# IO_master_nano.net
KiCad netlist of a schematic drawn in EAGLE
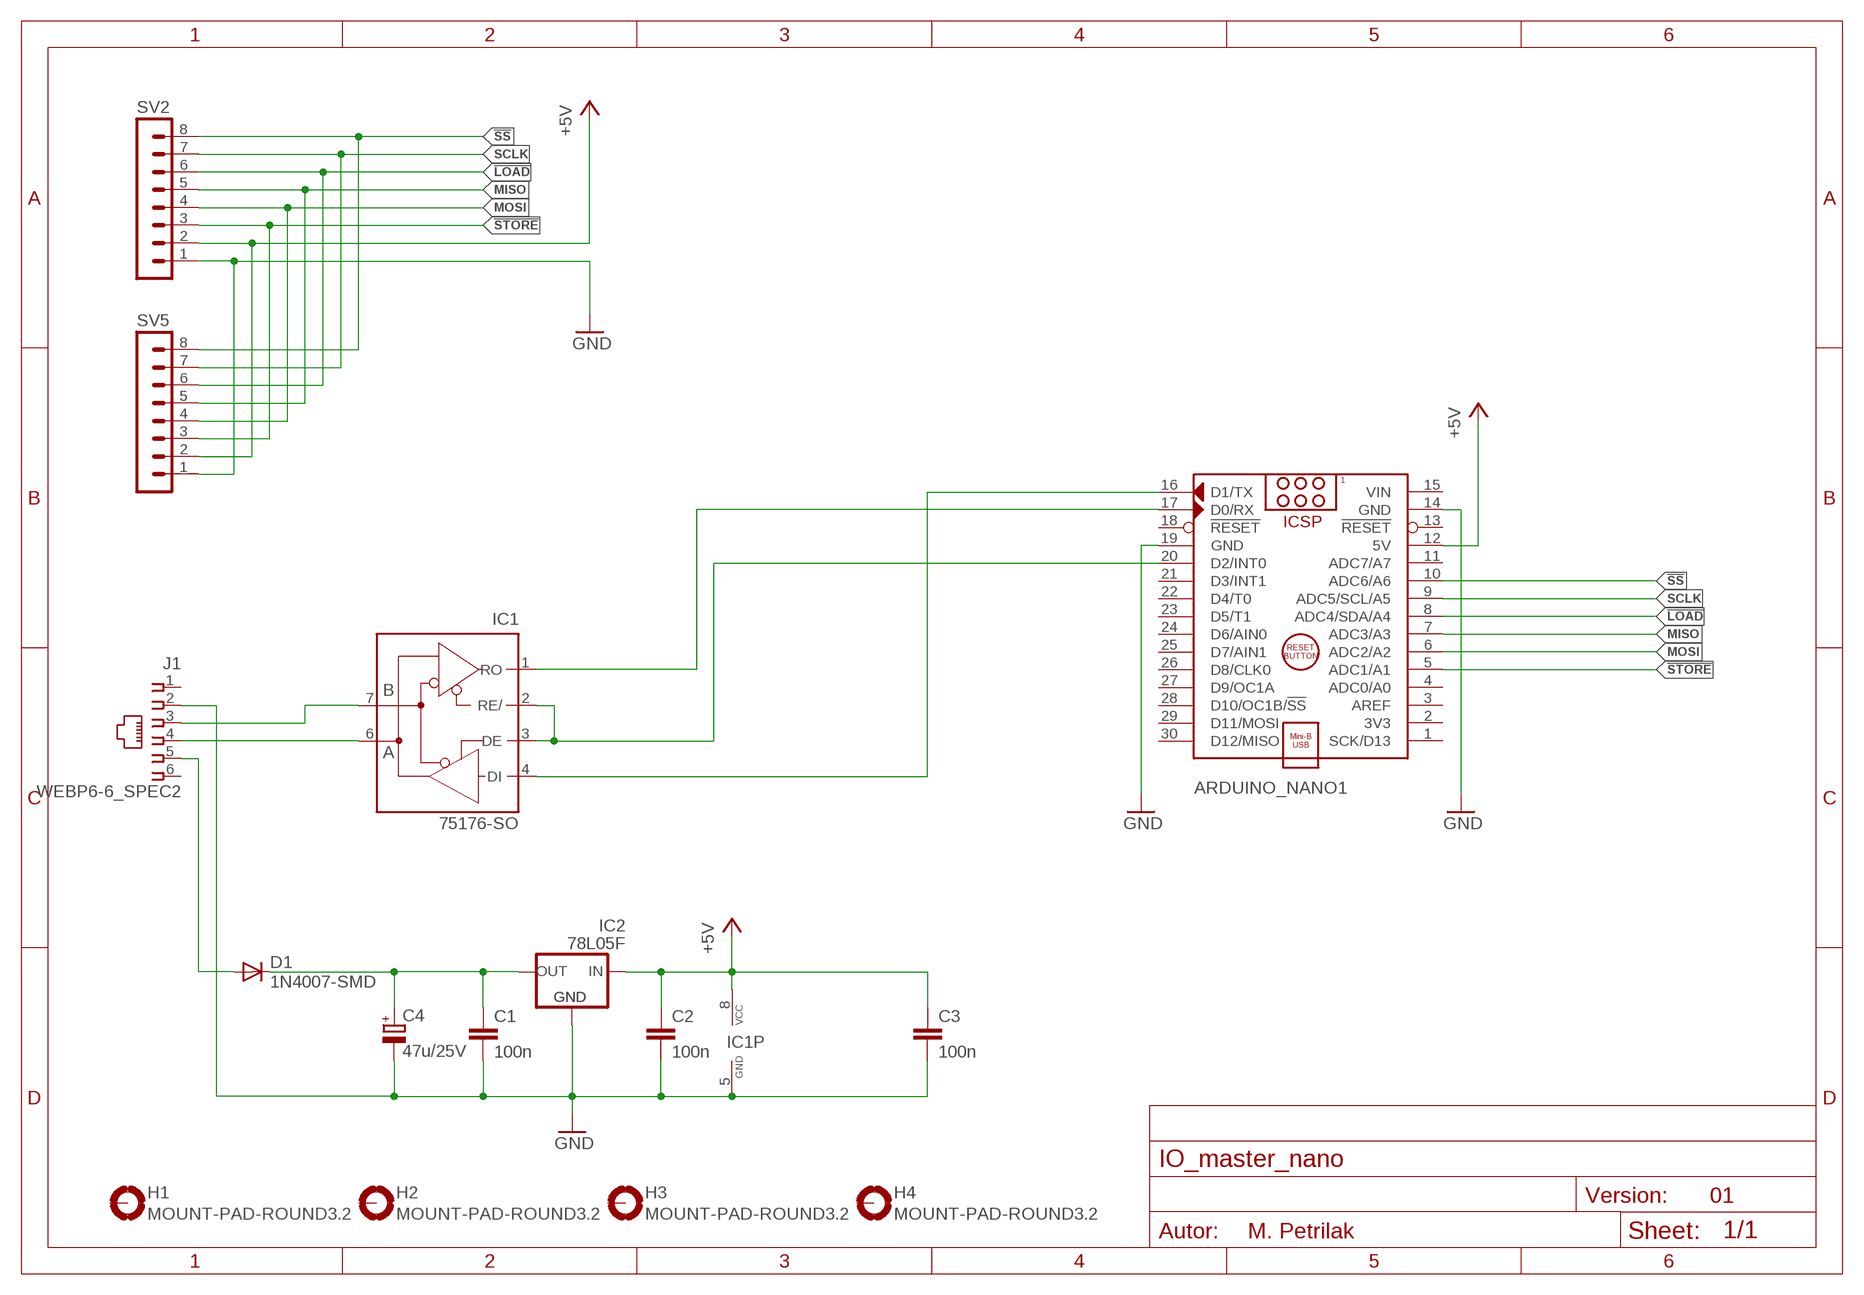
[diagram p0: schematic, sheet 1]

(export (version "E")
  (design (tool "Eeschema 10.0.6"))
  (components
    (comp (ref "ARDUINO_NANO1")
      (value "ARDUINO_NANO_2")
      (footprint "eagle-import:ARDUINO_NANO2")
      (libsource (lib "eagle-import") (part "ARDUINO_NANO_2"))
    )
    (comp (ref "C1")
      (value "100n")
      (footprint "eagle-import:C1206")
      (libsource (lib "eagle-import") (part "C-EUC1206"))
    )
    (comp (ref "C2")
      (value "100n")
      (footprint "eagle-import:C1206")
      (libsource (lib "eagle-import") (part "C-EUC1206"))
    )
    (comp (ref "C3")
      (value "100n")
      (footprint "eagle-import:C1206")
      (libsource (lib "eagle-import") (part "C-EUC1206"))
    )
    (comp (ref "C4")
      (value "47u/25V")
      (footprint "eagle-import:E2,5-6L")
      (libsource (lib "eagle-import") (part "CPOL-EUE2.5-6L"))
    )
    (comp (ref "D1")
      (value "1N4007-SMD")
      (footprint "eagle-import:SMA-DO214AC")
      (libsource (lib "eagle-import") (part "1N400-SMD7"))
    )
    (comp (ref "H1")
      (value "MOUNT-PAD-ROUND3.2")
      (footprint "eagle-import:3,2-PAD")
      (libsource (lib "eagle-import") (part "MOUNT-PAD-ROUND3.2"))
    )
    (comp (ref "H2")
      (value "MOUNT-PAD-ROUND3.2")
      (footprint "eagle-import:3,2-PAD")
      (libsource (lib "eagle-import") (part "MOUNT-PAD-ROUND3.2"))
    )
    (comp (ref "H3")
      (value "MOUNT-PAD-ROUND3.2")
      (footprint "eagle-import:3,2-PAD")
      (libsource (lib "eagle-import") (part "MOUNT-PAD-ROUND3.2"))
    )
    (comp (ref "H4")
      (value "MOUNT-PAD-ROUND3.2")
      (footprint "eagle-import:3,2-PAD")
      (libsource (lib "eagle-import") (part "MOUNT-PAD-ROUND3.2"))
    )
    (comp (ref "IC1")
      (value "75176-SO")
      (footprint "eagle-import:SO08")
      (libsource (lib "eagle-import") (part "75176-SO"))
    )
    (comp (ref "IC2")
      (value "78L05F")
      (footprint "eagle-import:SOT89")
      (libsource (lib "eagle-import") (part "78LF05"))
    )
    (comp (ref "J1")
      (value "WEBP6-6_SPEC2")
      (footprint "eagle-import:WEBP6-6_SPEC2")
      (libsource (lib "eagle-import") (part "WEBP6-6_SPEC2"))
    )
    (comp (ref "SV2")
      (value "MA08-1")
      (footprint "eagle-import:MA08-1")
      (libsource (lib "eagle-import") (part "MA08-1"))
    )
    (comp (ref "SV5")
      (value "MA08-1")
      (footprint "eagle-import:MA08-1")
      (libsource (lib "eagle-import") (part "MA08-1"))
    )
  )
  (nets
    (net (code "1") (name "+5V") (class "Default")
      (node (ref "ARDUINO_NANO1") (pin "12") (pinfunction "5V_12") (pintype "power_in"))
      (node (ref "C2") (pin "1") (pinfunction "1_1") (pintype "passive"))
      (node (ref "C3") (pin "1") (pinfunction "1_1") (pintype "passive"))
      (node (ref "IC1") (pin "8") (pinfunction "VCC_8") (pintype "power_in"))
      (node (ref "IC2") (pin "3") (pinfunction "VI_3") (pintype "input"))
      (node (ref "SV2") (pin "2") (pinfunction "2_2") (pintype "passive"))
      (node (ref "SV5") (pin "2") (pinfunction "2_2") (pintype "passive"))
    )
    (net (code "2") (name "/VIN") (class "Default")
      (node (ref "ARDUINO_NANO1") (pin "15") (pinfunction "VIN_15") (pintype "power_in"))
    )
    (net (code "3") (name "/~{LOAD}") (class "Default")
      (node (ref "ARDUINO_NANO1") (pin "8") (pinfunction "ADC4/SDA/A4_8") (pintype "bidirectional"))
      (node (ref "SV2") (pin "6") (pinfunction "6_6") (pintype "passive"))
      (node (ref "SV5") (pin "6") (pinfunction "6_6") (pintype "passive"))
    )
    (net (code "4") (name "/~{SS}") (class "Default")
      (node (ref "ARDUINO_NANO1") (pin "10") (pinfunction "ADC6/A6_10") (pintype "bidirectional"))
      (node (ref "SV2") (pin "8") (pinfunction "8_8") (pintype "passive"))
      (node (ref "SV5") (pin "8") (pinfunction "8_8") (pintype "passive"))
    )
    (net (code "5") (name "/~{STORE}") (class "Default")
      (node (ref "ARDUINO_NANO1") (pin "5") (pinfunction "ADC1/A1_5") (pintype "bidirectional"))
      (node (ref "SV2") (pin "3") (pinfunction "3_3") (pintype "passive"))
      (node (ref "SV5") (pin "3") (pinfunction "3_3") (pintype "passive"))
    )
    (net (code "6") (name "GND") (class "Default")
      (node (ref "ARDUINO_NANO1") (pin "14") (pinfunction "GND_14") (pintype "power_in"))
      (node (ref "ARDUINO_NANO1") (pin "19") (pinfunction "GND_19") (pintype "power_in"))
      (node (ref "C1") (pin "2") (pinfunction "2_2") (pintype "passive"))
      (node (ref "C2") (pin "2") (pinfunction "2_2") (pintype "passive"))
      (node (ref "C3") (pin "2") (pinfunction "2_2") (pintype "passive"))
      (node (ref "C4") (pin "-") (pinfunction "-_-") (pintype "passive"))
      (node (ref "IC1") (pin "5") (pinfunction "GND_5") (pintype "power_in"))
      (node (ref "IC2") (pin "2") (pinfunction "GND_2") (pintype "passive"))
      (node (ref "IC2") (pin "2@1") (pinfunction "GND_2@1") (pintype "passive"))
      (node (ref "J1") (pin "2") (pinfunction "2_2") (pintype "passive"))
      (node (ref "SV2") (pin "1") (pinfunction "1_1") (pintype "passive"))
      (node (ref "SV5") (pin "1") (pinfunction "1_1") (pintype "passive"))
    )
    (net (code "7") (name "MISO") (class "Default")
      (node (ref "ARDUINO_NANO1") (pin "7") (pinfunction "ADC3/A3_7") (pintype "bidirectional"))
      (node (ref "SV2") (pin "5") (pinfunction "5_5") (pintype "passive"))
      (node (ref "SV5") (pin "5") (pinfunction "5_5") (pintype "passive"))
    )
    (net (code "8") (name "MOSI") (class "Default")
      (node (ref "ARDUINO_NANO1") (pin "6") (pinfunction "ADC2/A2_6") (pintype "bidirectional"))
      (node (ref "SV2") (pin "4") (pinfunction "4_4") (pintype "passive"))
      (node (ref "SV5") (pin "4") (pinfunction "4_4") (pintype "passive"))
    )
    (net (code "9") (name "Net-(ARDUINO_NANO1-D0{slash}RX)") (class "Default")
      (node (ref "ARDUINO_NANO1") (pin "17") (pinfunction "D0/RX_17") (pintype "bidirectional"))
      (node (ref "IC1") (pin "1") (pinfunction "RO_1") (pintype "output"))
    )
    (net (code "10") (name "Net-(ARDUINO_NANO1-D1{slash}TX)") (class "Default")
      (node (ref "ARDUINO_NANO1") (pin "16") (pinfunction "D1/TX_16") (pintype "bidirectional"))
      (node (ref "IC1") (pin "4") (pinfunction "DI_4") (pintype "input"))
    )
    (net (code "11") (name "Net-(ARDUINO_NANO1-D2{slash}INT0)") (class "Default")
      (node (ref "ARDUINO_NANO1") (pin "20") (pinfunction "D2/INT0_20") (pintype "bidirectional"))
      (node (ref "IC1") (pin "2") (pinfunction "RE/_2") (pintype "input"))
      (node (ref "IC1") (pin "3") (pinfunction "DE_3") (pintype "input"))
    )
    (net (code "12") (name "Net-(D1-C)") (class "Default")
      (node (ref "C1") (pin "1") (pinfunction "1_1") (pintype "passive"))
      (node (ref "C4") (pin "+") (pinfunction "+_+") (pintype "passive"))
      (node (ref "D1") (pin "K") (pinfunction "C_K") (pintype "passive"))
      (node (ref "IC2") (pin "1") (pinfunction "VO_1") (pintype "passive"))
    )
    (net (code "13") (name "Net-(D1-PadA)") (class "Default")
      (node (ref "D1") (pin "A") (pinfunction "A_A") (pintype "passive"))
      (node (ref "J1") (pin "5") (pinfunction "5_5") (pintype "passive"))
    )
    (net (code "14") (name "Net-(IC1A-A)") (class "Default")
      (node (ref "IC1") (pin "6") (pinfunction "A_6") (pintype "passive"))
      (node (ref "J1") (pin "4") (pinfunction "4_4") (pintype "passive"))
    )
    (net (code "15") (name "Net-(IC1A-B)") (class "Default")
      (node (ref "IC1") (pin "7") (pinfunction "B_7") (pintype "passive"))
      (node (ref "J1") (pin "3") (pinfunction "3_3") (pintype "passive"))
    )
    (net (code "16") (name "SCLK") (class "Default")
      (node (ref "ARDUINO_NANO1") (pin "9") (pinfunction "ADC5/SCL/A5_9") (pintype "bidirectional"))
      (node (ref "SV2") (pin "7") (pinfunction "7_7") (pintype "passive"))
      (node (ref "SV5") (pin "7") (pinfunction "7_7") (pintype "passive"))
    )
    (net (code "17") (name "unconnected-(ARDUINO_NANO1-3V3-Pad2)") (class "Default")
      (node (ref "ARDUINO_NANO1") (pin "2") (pinfunction "3V3_2") (pintype "output"))
    )
    (net (code "18") (name "unconnected-(ARDUINO_NANO1-ADC0{slash}A0-Pad4)") (class "Default")
      (node (ref "ARDUINO_NANO1") (pin "4") (pinfunction "ADC0/A0_4") (pintype "bidirectional"))
    )
    (net (code "19") (name "unconnected-(ARDUINO_NANO1-ADC7{slash}A7-Pad11)") (class "Default")
      (node (ref "ARDUINO_NANO1") (pin "11") (pinfunction "ADC7/A7_11") (pintype "bidirectional"))
    )
    (net (code "20") (name "unconnected-(ARDUINO_NANO1-AREF-Pad3)") (class "Default")
      (node (ref "ARDUINO_NANO1") (pin "3") (pinfunction "AREF_3") (pintype "input"))
    )
    (net (code "21") (name "unconnected-(ARDUINO_NANO1-D3{slash}INT1-Pad21)") (class "Default")
      (node (ref "ARDUINO_NANO1") (pin "21") (pinfunction "D3/INT1_21") (pintype "bidirectional"))
    )
    (net (code "22") (name "unconnected-(ARDUINO_NANO1-D4{slash}T0-Pad22)") (class "Default")
      (node (ref "ARDUINO_NANO1") (pin "22") (pinfunction "D4/T0_22") (pintype "bidirectional"))
    )
    (net (code "23") (name "unconnected-(ARDUINO_NANO1-D5{slash}T1-Pad23)") (class "Default")
      (node (ref "ARDUINO_NANO1") (pin "23") (pinfunction "D5/T1_23") (pintype "bidirectional"))
    )
    (net (code "24") (name "unconnected-(ARDUINO_NANO1-D6{slash}AIN0-Pad24)") (class "Default")
      (node (ref "ARDUINO_NANO1") (pin "24") (pinfunction "D6/AIN0_24") (pintype "bidirectional"))
    )
    (net (code "25") (name "unconnected-(ARDUINO_NANO1-D7{slash}AIN1-Pad25)") (class "Default")
      (node (ref "ARDUINO_NANO1") (pin "25") (pinfunction "D7/AIN1_25") (pintype "bidirectional"))
    )
    (net (code "26") (name "unconnected-(ARDUINO_NANO1-D8{slash}CLK0-Pad26)") (class "Default")
      (node (ref "ARDUINO_NANO1") (pin "26") (pinfunction "D8/CLK0_26") (pintype "bidirectional"))
    )
    (net (code "27") (name "unconnected-(ARDUINO_NANO1-D9{slash}OC1A-Pad27)") (class "Default")
      (node (ref "ARDUINO_NANO1") (pin "27") (pinfunction "D9/OC1A_27") (pintype "bidirectional"))
    )
    (net (code "28") (name "unconnected-(ARDUINO_NANO1-D10{slash}OC1B{slash}~{SS}-Pad28)") (class "Default")
      (node (ref "ARDUINO_NANO1") (pin "28") (pinfunction "D10/OC1B/~{SS}_28") (pintype "bidirectional"))
    )
    (net (code "29") (name "unconnected-(ARDUINO_NANO1-D11{slash}MOSI-Pad29)") (class "Default")
      (node (ref "ARDUINO_NANO1") (pin "29") (pinfunction "D11/MOSI_29") (pintype "bidirectional"))
    )
    (net (code "30") (name "unconnected-(ARDUINO_NANO1-D12{slash}MISO-Pad30)") (class "Default")
      (node (ref "ARDUINO_NANO1") (pin "30") (pinfunction "D12/MISO_30") (pintype "bidirectional"))
    )
    (net (code "31") (name "unconnected-(ARDUINO_NANO1-SCK{slash}D13-Pad1)") (class "Default")
      (node (ref "ARDUINO_NANO1") (pin "1") (pinfunction "SCK/D13_1") (pintype "bidirectional"))
    )
    (net (code "32") (name "unconnected-(ARDUINO_NANO1-~{RESET}-Pad13)") (class "Default")
      (node (ref "ARDUINO_NANO1") (pin "13") (pinfunction "~{RESET}_13") (pintype "input"))
    )
    (net (code "33") (name "unconnected-(ARDUINO_NANO1-~{RESET}-Pad18)") (class "Default")
      (node (ref "ARDUINO_NANO1") (pin "18") (pinfunction "~{RESET}_18") (pintype "input"))
    )
    (net (code "34") (name "unconnected-(H1-MOUNT-PadB3,2)") (class "Default")
      (node (ref "H1") (pin "B3,2") (pinfunction "MOUNT_B3,2") (pintype "passive"))
    )
    (net (code "35") (name "unconnected-(H2-MOUNT-PadB3,2)") (class "Default")
      (node (ref "H2") (pin "B3,2") (pinfunction "MOUNT_B3,2") (pintype "passive"))
    )
    (net (code "36") (name "unconnected-(H3-MOUNT-PadB3,2)") (class "Default")
      (node (ref "H3") (pin "B3,2") (pinfunction "MOUNT_B3,2") (pintype "passive"))
    )
    (net (code "37") (name "unconnected-(H4-MOUNT-PadB3,2)") (class "Default")
      (node (ref "H4") (pin "B3,2") (pinfunction "MOUNT_B3,2") (pintype "passive"))
    )
    (net (code "38") (name "unconnected-(J1-Pad1)") (class "Default")
      (node (ref "J1") (pin "1") (pinfunction "1_1") (pintype "passive"))
    )
    (net (code "39") (name "unconnected-(J1-Pad6)") (class "Default")
      (node (ref "J1") (pin "6") (pinfunction "6_6") (pintype "passive"))
    )
  )
)
